# 7G_controller.net
KiCad netlist of a schematic drawn in EAGLE
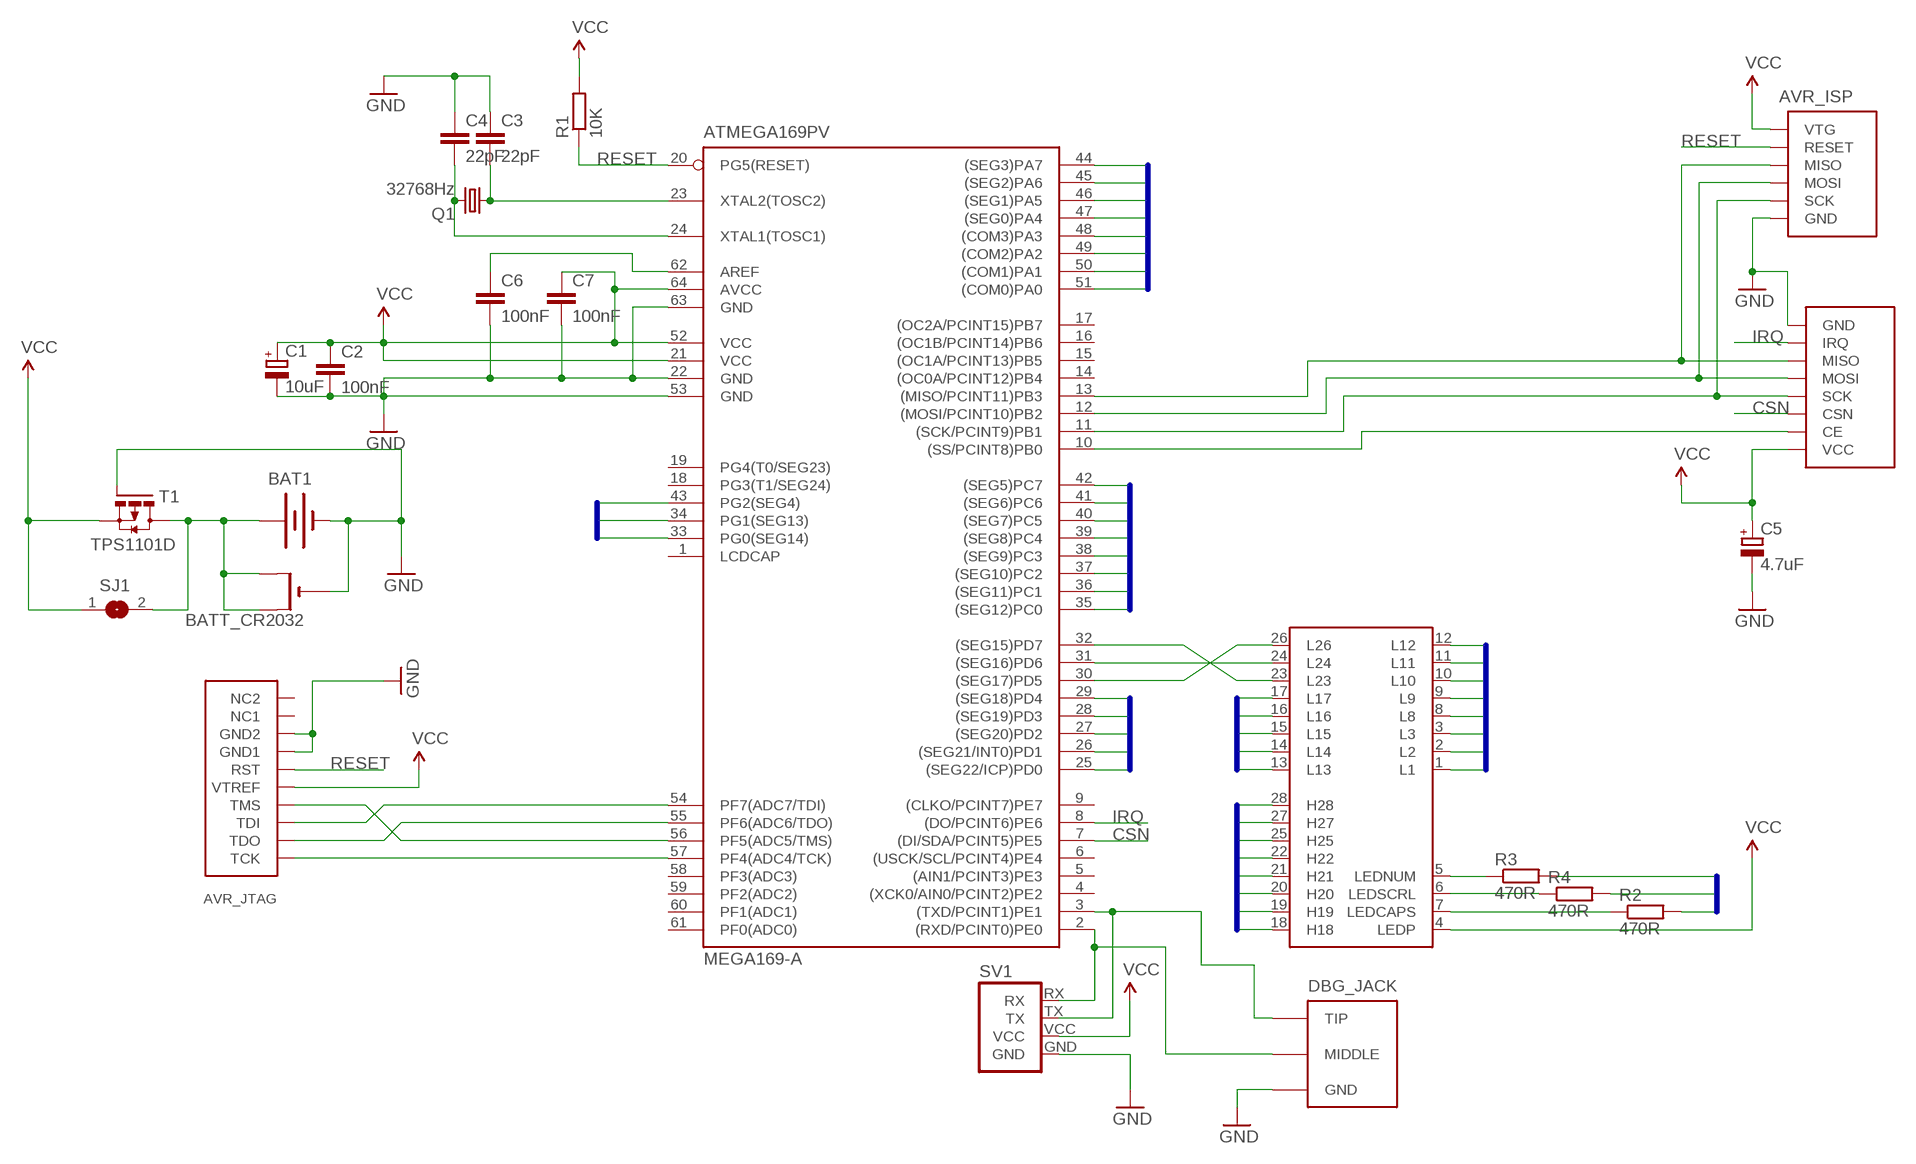
[diagram p0: schematic, sheet 1]

(export (version "E")
  (design (tool "Eeschema 10.0.6"))
  (components
    (comp (ref "ATMEGA169PV")
      (value "MEGA169-A")
      (footprint "eagle-import:TQFP64")
      (fields (field (name "MPN") "ATMEGA169PV-8AU"))
      (libsource (lib "eagle-import") (part "MEGA169-A"))
    )
    (comp (ref "AVR_ISP")
      (value "AVR-ISP-6SMALL_FP")
      (footprint "eagle-import:AVR-ISP-6-SMALL-FP")
      (libsource (lib "eagle-import") (part "AVR-ISP-6SMALL_FP"))
    )
    (comp (ref "AVR_JTAG")
      (value "AVR-JTAG")
      (footprint "eagle-import:AVR-JTAG")
      (libsource (lib "eagle-import") (part "AVR-JTAG"))
    )
    (comp (ref "BAT1")
      (value "BATTERYPLAIN")
      (footprint "eagle-import:BATTERY")
      (libsource (lib "eagle-import") (part "BATTERYPLAIN"))
    )
    (comp (ref "BATT_CR2032")
      (value "CR2032SMT")
      (footprint "eagle-import:CR2032-SMD")
      (libsource (lib "eagle-import") (part "CR2032SMT"))
    )
    (comp (ref "C1")
      (value "10uF")
      (footprint "eagle-import:SMC_B")
      (libsource (lib "eagle-import") (part "CPOL-EUSMCB"))
    )
    (comp (ref "C2")
      (value "100nF")
      (footprint "eagle-import:C0805")
      (libsource (lib "eagle-import") (part "C-EUC0805"))
    )
    (comp (ref "C3")
      (value "22pF")
      (footprint "eagle-import:C0805")
      (libsource (lib "eagle-import") (part "C-EUC0805"))
    )
    (comp (ref "C4")
      (value "22pF")
      (footprint "eagle-import:C0805")
      (libsource (lib "eagle-import") (part "C-EUC0805"))
    )
    (comp (ref "C5")
      (value "4.7uF")
      (footprint "eagle-import:SMC_B")
      (libsource (lib "eagle-import") (part "CPOL-EUSMCB"))
    )
    (comp (ref "C6")
      (value "100nF")
      (footprint "eagle-import:C0805")
      (libsource (lib "eagle-import") (part "C-EUC0805"))
    )
    (comp (ref "C7")
      (value "100nF")
      (footprint "eagle-import:C0805")
      (libsource (lib "eagle-import") (part "C-EUC0805"))
    )
    (comp (ref "DBG_JACK")
      (value "JACK_FEMALE_3.5MMCHEAP")
      (footprint "eagle-import:JACK_CHEAP")
      (libsource (lib "eagle-import") (part "JACK_FEMALE_3.5MMCHEAP"))
    )
    (comp (ref "MTRX_CONN")
      (value "SS7G_CONNSMD")
      (footprint "eagle-import:SS7G_CONN_SMD")
      (libsource (lib "eagle-import") (part "SS7G_CONNSMD"))
    )
    (comp (ref "NRF24L01")
      (value "NRF24L01_MOD_NINE_EAGLESGENERIC")
      (footprint "eagle-import:NRF24L01_MOD_GENERIC")
      (libsource (lib "eagle-import") (part "NRF24L01_MOD_NINE_EAGLESGENERIC"))
    )
    (comp (ref "Q1")
      (value "32768Hz")
      (footprint "eagle-import:NSK_QUARTZ_CLOCK")
      (libsource (lib "eagle-import") (part "CRYSTAL"))
    )
    (comp (ref "R1")
      (value "10K")
      (footprint "eagle-import:R0805")
      (libsource (lib "eagle-import") (part "R-EU_R0805"))
    )
    (comp (ref "R2")
      (value "470R")
      (footprint "eagle-import:R0805")
      (libsource (lib "eagle-import") (part "R-EU_R0805"))
    )
    (comp (ref "R3")
      (value "470R")
      (footprint "eagle-import:R0805")
      (libsource (lib "eagle-import") (part "R-EU_R0805"))
    )
    (comp (ref "R4")
      (value "470R")
      (footprint "eagle-import:R0805")
      (libsource (lib "eagle-import") (part "R-EU_R0805"))
    )
    (comp (ref "SJ1") (value "SJ") (footprint "eagle-import:SJ") (libsource (lib "eagle-import") (part "SJ")))
    (comp (ref "SV1")
      (value "UART_PORT")
      (footprint "eagle-import:UART_PORT")
      (libsource (lib "eagle-import") (part "UART_PORT"))
    )
    (comp (ref "T1")
      (value "TPS1101D")
      (footprint "eagle-import:SO8")
      (libsource (lib "eagle-import") (part "TPS1101D"))
    )
  )
  (nets
    (net (code "1") (name "/CAPS") (class "Default")
      (node (ref "ATMEGA169PV") (pin "43") (pinfunction "PG2(SEG4)_43") (pintype "bidirectional"))
      (node (ref "R2") (pin "2") (pinfunction "2_2") (pintype "passive"))
    )
    (net (code "2") (name "/CSN") (class "Default")
      (node (ref "ATMEGA169PV") (pin "7") (pinfunction "(DI/SDA/PCINT5)PE5_7") (pintype "bidirectional"))
      (node (ref "NRF24L01") (pin "CSN") (pinfunction "CSN_CSN") (pintype "input"))
    )
    (net (code "3") (name "/H18") (class "Default")
      (node (ref "ATMEGA169PV") (pin "42") (pinfunction "(SEG5)PC7_42") (pintype "output"))
      (node (ref "MTRX_CONN") (pin "18") (pinfunction "H18_18") (pintype "bidirectional"))
    )
    (net (code "4") (name "/H19") (class "Default")
      (node (ref "ATMEGA169PV") (pin "41") (pinfunction "(SEG6)PC6_41") (pintype "output"))
      (node (ref "MTRX_CONN") (pin "19") (pinfunction "H19_19") (pintype "bidirectional"))
    )
    (net (code "5") (name "/H20") (class "Default")
      (node (ref "ATMEGA169PV") (pin "40") (pinfunction "(SEG7)PC5_40") (pintype "output"))
      (node (ref "MTRX_CONN") (pin "20") (pinfunction "H20_20") (pintype "bidirectional"))
    )
    (net (code "6") (name "/H21") (class "Default")
      (node (ref "ATMEGA169PV") (pin "38") (pinfunction "(SEG9)PC3_38") (pintype "output"))
      (node (ref "MTRX_CONN") (pin "21") (pinfunction "H21_21") (pintype "bidirectional"))
    )
    (net (code "7") (name "/H22") (class "Default")
      (node (ref "ATMEGA169PV") (pin "36") (pinfunction "(SEG11)PC1_36") (pintype "output"))
      (node (ref "MTRX_CONN") (pin "22") (pinfunction "H22_22") (pintype "bidirectional"))
    )
    (net (code "8") (name "/H25") (class "Default")
      (node (ref "ATMEGA169PV") (pin "35") (pinfunction "(SEG12)PC0_35") (pintype "output"))
      (node (ref "MTRX_CONN") (pin "25") (pinfunction "H25_25") (pintype "bidirectional"))
    )
    (net (code "9") (name "/H27") (class "Default")
      (node (ref "ATMEGA169PV") (pin "37") (pinfunction "(SEG10)PC2_37") (pintype "output"))
      (node (ref "MTRX_CONN") (pin "27") (pinfunction "H27_27") (pintype "bidirectional"))
    )
    (net (code "10") (name "/H28") (class "Default")
      (node (ref "ATMEGA169PV") (pin "39") (pinfunction "(SEG8)PC4_39") (pintype "output"))
      (node (ref "MTRX_CONN") (pin "28") (pinfunction "H28_28") (pintype "bidirectional"))
    )
    (net (code "11") (name "/IRQ") (class "Default")
      (node (ref "ATMEGA169PV") (pin "8") (pinfunction "(DO/PCINT6)PE6_8") (pintype "bidirectional"))
      (node (ref "NRF24L01") (pin "IRQ") (pinfunction "IRQ_IRQ") (pintype "output"))
    )
    (net (code "12") (name "/L1") (class "Default")
      (node (ref "ATMEGA169PV") (pin "50") (pinfunction "(COM1)PA1_50") (pintype "bidirectional"))
      (node (ref "MTRX_CONN") (pin "1") (pinfunction "L1_1") (pintype "bidirectional"))
    )
    (net (code "13") (name "/L2") (class "Default")
      (node (ref "ATMEGA169PV") (pin "48") (pinfunction "(COM3)PA3_48") (pintype "bidirectional"))
      (node (ref "MTRX_CONN") (pin "2") (pinfunction "L2_2") (pintype "bidirectional"))
    )
    (net (code "14") (name "/L3") (class "Default")
      (node (ref "ATMEGA169PV") (pin "46") (pinfunction "(SEG1)PA5_46") (pintype "bidirectional"))
      (node (ref "MTRX_CONN") (pin "3") (pinfunction "L3_3") (pintype "bidirectional"))
    )
    (net (code "15") (name "/L8") (class "Default")
      (node (ref "ATMEGA169PV") (pin "45") (pinfunction "(SEG2)PA6_45") (pintype "bidirectional"))
      (node (ref "MTRX_CONN") (pin "8") (pinfunction "L8_8") (pintype "bidirectional"))
    )
    (net (code "16") (name "/L9") (class "Default")
      (node (ref "ATMEGA169PV") (pin "44") (pinfunction "(SEG3)PA7_44") (pintype "bidirectional"))
      (node (ref "MTRX_CONN") (pin "9") (pinfunction "L9_9") (pintype "bidirectional"))
    )
    (net (code "17") (name "/L10") (class "Default")
      (node (ref "ATMEGA169PV") (pin "25") (pinfunction "(SEG22/ICP)PD0_25") (pintype "bidirectional"))
      (node (ref "MTRX_CONN") (pin "10") (pinfunction "L10_10") (pintype "bidirectional"))
    )
    (net (code "18") (name "/L11") (class "Default")
      (node (ref "ATMEGA169PV") (pin "26") (pinfunction "(SEG21/INT0)PD1_26") (pintype "bidirectional"))
      (node (ref "MTRX_CONN") (pin "11") (pinfunction "L11_11") (pintype "bidirectional"))
    )
    (net (code "19") (name "/L12") (class "Default")
      (node (ref "ATMEGA169PV") (pin "27") (pinfunction "(SEG20)PD2_27") (pintype "bidirectional"))
      (node (ref "MTRX_CONN") (pin "12") (pinfunction "L12_12") (pintype "bidirectional"))
    )
    (net (code "20") (name "/L13") (class "Default")
      (node (ref "ATMEGA169PV") (pin "28") (pinfunction "(SEG19)PD3_28") (pintype "bidirectional"))
      (node (ref "MTRX_CONN") (pin "13") (pinfunction "L13_13") (pintype "bidirectional"))
    )
    (net (code "21") (name "/L14") (class "Default")
      (node (ref "ATMEGA169PV") (pin "29") (pinfunction "(SEG18)PD4_29") (pintype "bidirectional"))
      (node (ref "MTRX_CONN") (pin "14") (pinfunction "L14_14") (pintype "bidirectional"))
    )
    (net (code "22") (name "/L15") (class "Default")
      (node (ref "ATMEGA169PV") (pin "51") (pinfunction "(COM0)PA0_51") (pintype "bidirectional"))
      (node (ref "MTRX_CONN") (pin "15") (pinfunction "L15_15") (pintype "bidirectional"))
    )
    (net (code "23") (name "/L16") (class "Default")
      (node (ref "ATMEGA169PV") (pin "49") (pinfunction "(COM2)PA2_49") (pintype "bidirectional"))
      (node (ref "MTRX_CONN") (pin "16") (pinfunction "L16_16") (pintype "bidirectional"))
    )
    (net (code "24") (name "/L17") (class "Default")
      (node (ref "ATMEGA169PV") (pin "47") (pinfunction "(SEG0)PA4_47") (pintype "bidirectional"))
      (node (ref "MTRX_CONN") (pin "17") (pinfunction "L17_17") (pintype "bidirectional"))
    )
    (net (code "25") (name "/NUML") (class "Default")
      (node (ref "ATMEGA169PV") (pin "33") (pinfunction "PG0(SEG14)_33") (pintype "bidirectional"))
      (node (ref "R3") (pin "2") (pinfunction "2_2") (pintype "passive"))
    )
    (net (code "26") (name "/RESET") (class "Default")
      (node (ref "ATMEGA169PV") (pin "20") (pinfunction "PG5(RESET)_20") (pintype "input"))
      (node (ref "AVR_ISP") (pin "RESET") (pinfunction "RESET_RESET") (pintype "passive"))
      (node (ref "AVR_JTAG") (pin "P$6") (pinfunction "RST_P$6") (pintype "bidirectional"))
      (node (ref "R1") (pin "1") (pinfunction "1_1") (pintype "passive"))
    )
    (net (code "27") (name "/SCRL") (class "Default")
      (node (ref "ATMEGA169PV") (pin "34") (pinfunction "PG1(SEG13)_34") (pintype "bidirectional"))
      (node (ref "R4") (pin "2") (pinfunction "2_2") (pintype "passive"))
    )
    (net (code "28") (name "GND") (class "Default")
      (node (ref "ATMEGA169PV") (pin "22") (pinfunction "GND_22") (pintype "power_in"))
      (node (ref "ATMEGA169PV") (pin "53") (pinfunction "GND_53") (pintype "power_in"))
      (node (ref "ATMEGA169PV") (pin "63") (pinfunction "GND_63") (pintype "power_in"))
      (node (ref "AVR_ISP") (pin "GND") (pinfunction "GND_GND") (pintype "passive"))
      (node (ref "AVR_JTAG") (pin "P$10") (pinfunction "GND2_P$10") (pintype "power_in"))
      (node (ref "AVR_JTAG") (pin "P$2") (pinfunction "GND1_P$2") (pintype "power_in"))
      (node (ref "BAT1") (pin "-") (pinfunction "-_-") (pintype "power_in"))
      (node (ref "BATT_CR2032") (pin "-") (pinfunction "-_-") (pintype "passive"))
      (node (ref "C1") (pin "-") (pinfunction "-_-") (pintype "passive"))
      (node (ref "C2") (pin "2") (pinfunction "2_2") (pintype "passive"))
      (node (ref "C3") (pin "1") (pinfunction "1_1") (pintype "passive"))
      (node (ref "C4") (pin "1") (pinfunction "1_1") (pintype "passive"))
      (node (ref "C5") (pin "-") (pinfunction "-_-") (pintype "passive"))
      (node (ref "C6") (pin "2") (pinfunction "2_2") (pintype "passive"))
      (node (ref "C7") (pin "2") (pinfunction "2_2") (pintype "passive"))
      (node (ref "DBG_JACK") (pin "1") (pinfunction "GND_1") (pintype "bidirectional"))
      (node (ref "NRF24L01") (pin "GND") (pinfunction "GND_GND") (pintype "power_in"))
      (node (ref "SV1") (pin "GND") (pinfunction "GND_GND") (pintype "passive"))
      (node (ref "T1") (pin "4") (pinfunction "G_4") (pintype "passive"))
    )
    (net (code "29") (name "Net-(ATMEGA169PV-(MISO{slash}PCINT11)PB3)") (class "Default")
      (node (ref "ATMEGA169PV") (pin "13") (pinfunction "(MISO/PCINT11)PB3_13") (pintype "bidirectional"))
      (node (ref "AVR_ISP") (pin "MISO") (pinfunction "MISO_MISO") (pintype "passive"))
      (node (ref "NRF24L01") (pin "MISO") (pinfunction "MISO_MISO") (pintype "output"))
    )
    (net (code "30") (name "Net-(ATMEGA169PV-(MOSI{slash}PCINT10)PB2)") (class "Default")
      (node (ref "ATMEGA169PV") (pin "12") (pinfunction "(MOSI/PCINT10)PB2_12") (pintype "bidirectional"))
      (node (ref "AVR_ISP") (pin "MOSI") (pinfunction "MOSI_MOSI") (pintype "passive"))
      (node (ref "NRF24L01") (pin "MOSI") (pinfunction "MOSI_MOSI") (pintype "input"))
    )
    (net (code "31") (name "Net-(ATMEGA169PV-(RXD{slash}PCINT0)PE0)") (class "Default")
      (node (ref "ATMEGA169PV") (pin "2") (pinfunction "(RXD/PCINT0)PE0_2") (pintype "bidirectional"))
      (node (ref "DBG_JACK") (pin "4") (pinfunction "MIDDLE_4") (pintype "bidirectional"))
      (node (ref "SV1") (pin "RX") (pinfunction "RX_RX") (pintype "passive"))
    )
    (net (code "32") (name "Net-(ATMEGA169PV-(SCK{slash}PCINT9)PB1)") (class "Default")
      (node (ref "ATMEGA169PV") (pin "11") (pinfunction "(SCK/PCINT9)PB1_11") (pintype "bidirectional"))
      (node (ref "AVR_ISP") (pin "SCK") (pinfunction "SCK_SCK") (pintype "passive"))
      (node (ref "NRF24L01") (pin "SCK") (pinfunction "SCK_SCK") (pintype "input"))
    )
    (net (code "33") (name "Net-(ATMEGA169PV-(SEG15)PD7)") (class "Default")
      (node (ref "ATMEGA169PV") (pin "32") (pinfunction "(SEG15)PD7_32") (pintype "bidirectional"))
      (node (ref "MTRX_CONN") (pin "23") (pinfunction "L23_23") (pintype "bidirectional"))
    )
    (net (code "34") (name "Net-(ATMEGA169PV-(SEG16)PD6)") (class "Default")
      (node (ref "ATMEGA169PV") (pin "31") (pinfunction "(SEG16)PD6_31") (pintype "bidirectional"))
      (node (ref "MTRX_CONN") (pin "24") (pinfunction "L24_24") (pintype "bidirectional"))
    )
    (net (code "35") (name "Net-(ATMEGA169PV-(SEG17)PD5)") (class "Default")
      (node (ref "ATMEGA169PV") (pin "30") (pinfunction "(SEG17)PD5_30") (pintype "bidirectional"))
      (node (ref "MTRX_CONN") (pin "26") (pinfunction "L26_26") (pintype "bidirectional"))
    )
    (net (code "36") (name "Net-(ATMEGA169PV-(SS{slash}PCINT8)PB0)") (class "Default")
      (node (ref "ATMEGA169PV") (pin "10") (pinfunction "(SS/PCINT8)PB0_10") (pintype "bidirectional"))
      (node (ref "NRF24L01") (pin "CE") (pinfunction "CE_CE") (pintype "input"))
    )
    (net (code "37") (name "Net-(ATMEGA169PV-(TXD{slash}PCINT1)PE1)") (class "Default")
      (node (ref "ATMEGA169PV") (pin "3") (pinfunction "(TXD/PCINT1)PE1_3") (pintype "bidirectional"))
      (node (ref "DBG_JACK") (pin "2") (pinfunction "TIP_2") (pintype "bidirectional"))
      (node (ref "DBG_JACK") (pin "3") (pinfunction "TIP_3") (pintype "bidirectional"))
      (node (ref "SV1") (pin "TX") (pinfunction "TX_TX") (pintype "passive"))
    )
    (net (code "38") (name "Net-(ATMEGA169PV-AREF)") (class "Default")
      (node (ref "ATMEGA169PV") (pin "62") (pinfunction "AREF_62") (pintype "passive"))
      (node (ref "C6") (pin "1") (pinfunction "1_1") (pintype "passive"))
    )
    (net (code "39") (name "Net-(ATMEGA169PV-PF4(ADC4{slash}TCK))") (class "Default")
      (node (ref "ATMEGA169PV") (pin "57") (pinfunction "PF4(ADC4/TCK)_57") (pintype "input"))
      (node (ref "AVR_JTAG") (pin "P$1") (pinfunction "TCK_P$1") (pintype "bidirectional"))
    )
    (net (code "40") (name "Net-(ATMEGA169PV-PF5(ADC5{slash}TMS))") (class "Default")
      (node (ref "ATMEGA169PV") (pin "56") (pinfunction "PF5(ADC5/TMS)_56") (pintype "input"))
      (node (ref "AVR_JTAG") (pin "P$5") (pinfunction "TMS_P$5") (pintype "bidirectional"))
    )
    (net (code "41") (name "Net-(ATMEGA169PV-PF6(ADC6{slash}TDO))") (class "Default")
      (node (ref "ATMEGA169PV") (pin "55") (pinfunction "PF6(ADC6/TDO)_55") (pintype "input"))
      (node (ref "AVR_JTAG") (pin "P$3") (pinfunction "TDO_P$3") (pintype "bidirectional"))
    )
    (net (code "42") (name "Net-(ATMEGA169PV-PF7(ADC7{slash}TDI))") (class "Default")
      (node (ref "ATMEGA169PV") (pin "54") (pinfunction "PF7(ADC7/TDI)_54") (pintype "input"))
      (node (ref "AVR_JTAG") (pin "P$9") (pinfunction "TDI_P$9") (pintype "bidirectional"))
    )
    (net (code "43") (name "Net-(ATMEGA169PV-XTAL1(TOSC1))") (class "Default")
      (node (ref "ATMEGA169PV") (pin "24") (pinfunction "XTAL1(TOSC1)_24") (pintype "bidirectional"))
      (node (ref "C4") (pin "2") (pinfunction "2_2") (pintype "passive"))
      (node (ref "Q1") (pin "4") (pinfunction "2_4") (pintype "passive"))
    )
    (net (code "44") (name "Net-(ATMEGA169PV-XTAL2(TOSC2))") (class "Default")
      (node (ref "ATMEGA169PV") (pin "23") (pinfunction "XTAL2(TOSC2)_23") (pintype "bidirectional"))
      (node (ref "C3") (pin "2") (pinfunction "2_2") (pintype "passive"))
      (node (ref "Q1") (pin "1") (pinfunction "1_1") (pintype "passive"))
    )
    (net (code "45") (name "Net-(BATT_CR2032-+)") (class "Default")
      (node (ref "BAT1") (pin "+") (pinfunction "+_+") (pintype "power_in"))
      (node (ref "BATT_CR2032") (pin "+$1") (pinfunction "+_+$1") (pintype "passive"))
      (node (ref "BATT_CR2032") (pin "+$2") (pinfunction "+1_+$2") (pintype "passive"))
      (node (ref "SJ1") (pin "2") (pinfunction "2_2") (pintype "passive"))
      (node (ref "T1") (pin "5") (pinfunction "D_5") (pintype "passive"))
      (node (ref "T1") (pin "6") (pinfunction "D_6") (pintype "passive"))
      (node (ref "T1") (pin "7") (pinfunction "D_7") (pintype "passive"))
      (node (ref "T1") (pin "8") (pinfunction "D_8") (pintype "passive"))
    )
    (net (code "46") (name "Net-(MTRX_CONN-LEDCAPS)") (class "Default")
      (node (ref "MTRX_CONN") (pin "7") (pinfunction "LEDCAPS_7") (pintype "bidirectional"))
      (node (ref "R2") (pin "1") (pinfunction "1_1") (pintype "passive"))
    )
    (net (code "47") (name "Net-(MTRX_CONN-LEDNUM)") (class "Default")
      (node (ref "MTRX_CONN") (pin "5") (pinfunction "LEDNUM_5") (pintype "bidirectional"))
      (node (ref "R3") (pin "1") (pinfunction "1_1") (pintype "passive"))
    )
    (net (code "48") (name "Net-(MTRX_CONN-LEDSCRL)") (class "Default")
      (node (ref "MTRX_CONN") (pin "6") (pinfunction "LEDSCRL_6") (pintype "bidirectional"))
      (node (ref "R4") (pin "1") (pinfunction "1_1") (pintype "passive"))
    )
    (net (code "49") (name "VCC") (class "Default")
      (node (ref "ATMEGA169PV") (pin "21") (pinfunction "VCC_21") (pintype "power_in"))
      (node (ref "ATMEGA169PV") (pin "52") (pinfunction "VCC_52") (pintype "power_in"))
      (node (ref "ATMEGA169PV") (pin "64") (pinfunction "AVCC_64") (pintype "power_in"))
      (node (ref "AVR_ISP") (pin "VCC") (pinfunction "VTG_VCC") (pintype "passive"))
      (node (ref "AVR_JTAG") (pin "P$4") (pinfunction "VTREF_P$4") (pintype "bidirectional"))
      (node (ref "C1") (pin "+") (pinfunction "+_+") (pintype "passive"))
      (node (ref "C2") (pin "1") (pinfunction "1_1") (pintype "passive"))
      (node (ref "C5") (pin "+") (pinfunction "+_+") (pintype "passive"))
      (node (ref "C7") (pin "1") (pinfunction "1_1") (pintype "passive"))
      (node (ref "MTRX_CONN") (pin "4") (pinfunction "LEDP_4") (pintype "bidirectional"))
      (node (ref "NRF24L01") (pin "+3.3V") (pinfunction "VCC_+3.3V") (pintype "power_in"))
      (node (ref "R1") (pin "2") (pinfunction "2_2") (pintype "passive"))
      (node (ref "SJ1") (pin "1") (pinfunction "1_1") (pintype "passive"))
      (node (ref "SV1") (pin "VCC") (pinfunction "VCC_VCC") (pintype "passive"))
      (node (ref "T1") (pin "1") (pinfunction "S_1") (pintype "passive"))
      (node (ref "T1") (pin "2") (pinfunction "S_2") (pintype "passive"))
      (node (ref "T1") (pin "3") (pinfunction "S_3") (pintype "passive"))
    )
    (net (code "50") (name "unconnected-(ATMEGA169PV-(AIN1{slash}PCINT3)PE3-Pad5)") (class "Default")
      (node (ref "ATMEGA169PV") (pin "5") (pinfunction "(AIN1/PCINT3)PE3_5") (pintype "bidirectional"))
    )
    (net (code "51") (name "unconnected-(ATMEGA169PV-(CLKO{slash}PCINT7)PE7-Pad9)") (class "Default")
      (node (ref "ATMEGA169PV") (pin "9") (pinfunction "(CLKO/PCINT7)PE7_9") (pintype "bidirectional"))
    )
    (net (code "52") (name "unconnected-(ATMEGA169PV-(OC0A{slash}PCINT12)PB4-Pad14)") (class "Default")
      (node (ref "ATMEGA169PV") (pin "14") (pinfunction "(OC0A/PCINT12)PB4_14") (pintype "bidirectional"))
    )
    (net (code "53") (name "unconnected-(ATMEGA169PV-(OC1A{slash}PCINT13)PB5-Pad15)") (class "Default")
      (node (ref "ATMEGA169PV") (pin "15") (pinfunction "(OC1A/PCINT13)PB5_15") (pintype "bidirectional"))
    )
    (net (code "54") (name "unconnected-(ATMEGA169PV-(OC1B{slash}PCINT14)PB6-Pad16)") (class "Default")
      (node (ref "ATMEGA169PV") (pin "16") (pinfunction "(OC1B/PCINT14)PB6_16") (pintype "bidirectional"))
    )
    (net (code "55") (name "unconnected-(ATMEGA169PV-(OC2A{slash}PCINT15)PB7-Pad17)") (class "Default")
      (node (ref "ATMEGA169PV") (pin "17") (pinfunction "(OC2A/PCINT15)PB7_17") (pintype "bidirectional"))
    )
    (net (code "56") (name "unconnected-(ATMEGA169PV-(USCK{slash}SCL{slash}PCINT4)PE4-Pad6)") (class "Default")
      (node (ref "ATMEGA169PV") (pin "6") (pinfunction "(USCK/SCL/PCINT4)PE4_6") (pintype "bidirectional"))
    )
    (net (code "57") (name "unconnected-(ATMEGA169PV-(XCK0{slash}AIN0{slash}PCINT2)PE2-Pad4)") (class "Default")
      (node (ref "ATMEGA169PV") (pin "4") (pinfunction "(XCK0/AIN0/PCINT2)PE2_4") (pintype "bidirectional"))
    )
    (net (code "58") (name "unconnected-(ATMEGA169PV-LCDCAP-Pad1)") (class "Default")
      (node (ref "ATMEGA169PV") (pin "1") (pinfunction "LCDCAP_1") (pintype "input"))
    )
    (net (code "59") (name "unconnected-(ATMEGA169PV-PF0(ADC0)-Pad61)") (class "Default")
      (node (ref "ATMEGA169PV") (pin "61") (pinfunction "PF0(ADC0)_61") (pintype "input"))
    )
    (net (code "60") (name "unconnected-(ATMEGA169PV-PF1(ADC1)-Pad60)") (class "Default")
      (node (ref "ATMEGA169PV") (pin "60") (pinfunction "PF1(ADC1)_60") (pintype "input"))
    )
    (net (code "61") (name "unconnected-(ATMEGA169PV-PF2(ADC2)-Pad59)") (class "Default")
      (node (ref "ATMEGA169PV") (pin "59") (pinfunction "PF2(ADC2)_59") (pintype "input"))
    )
    (net (code "62") (name "unconnected-(ATMEGA169PV-PF3(ADC3)-Pad58)") (class "Default")
      (node (ref "ATMEGA169PV") (pin "58") (pinfunction "PF3(ADC3)_58") (pintype "input"))
    )
    (net (code "63") (name "unconnected-(ATMEGA169PV-PG3(T1{slash}SEG24)-Pad18)") (class "Default")
      (node (ref "ATMEGA169PV") (pin "18") (pinfunction "PG3(T1/SEG24)_18") (pintype "bidirectional"))
    )
    (net (code "64") (name "unconnected-(ATMEGA169PV-PG4(T0{slash}SEG23)-Pad19)") (class "Default")
      (node (ref "ATMEGA169PV") (pin "19") (pinfunction "PG4(T0/SEG23)_19") (pintype "bidirectional"))
    )
    (net (code "65") (name "unconnected-(AVR_JTAG-NC1-PadP$7)") (class "Default")
      (node (ref "AVR_JTAG") (pin "P$7") (pinfunction "NC1_P$7") (pintype "no_connect"))
    )
    (net (code "66") (name "unconnected-(AVR_JTAG-NC2-PadP$8)") (class "Default")
      (node (ref "AVR_JTAG") (pin "P$8") (pinfunction "NC2_P$8") (pintype "no_connect"))
    )
  )
)
